# motor_ic.net
KiCad netlist of a schematic drawn in EAGLE
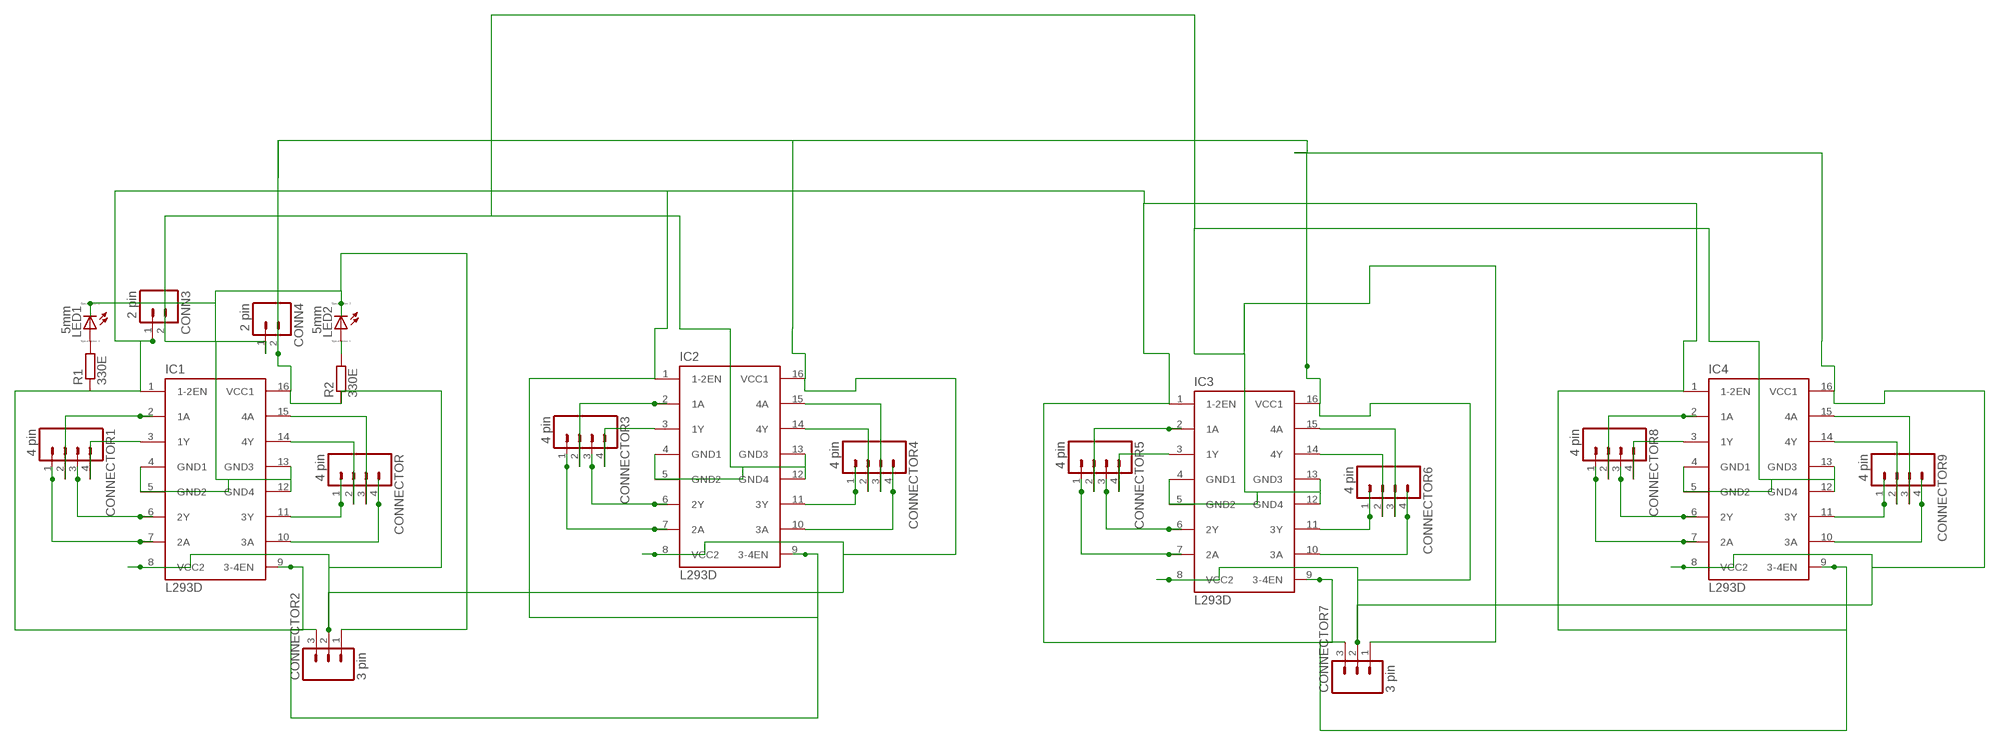
[diagram p0: schematic, sheet 1]

(export (version "E")
  (design (tool "Eeschema 10.0.6"))
  (components
    (comp (ref "CONN3")
      (value "2 pin")
      (footprint "eagle-import:02P")
      (libsource (lib "eagle-import") (part "M02"))
    )
    (comp (ref "CONN4")
      (value "2 pin")
      (footprint "eagle-import:02P")
      (libsource (lib "eagle-import") (part "M02"))
    )
    (comp (ref "CONNECTOR")
      (value "4 pin")
      (footprint "eagle-import:04P")
      (libsource (lib "eagle-import") (part "M04"))
    )
    (comp (ref "CONNECTOR1")
      (value "4 pin")
      (footprint "eagle-import:04P")
      (libsource (lib "eagle-import") (part "M04"))
    )
    (comp (ref "CONNECTOR2")
      (value "3 pin")
      (footprint "eagle-import:03P")
      (libsource (lib "eagle-import") (part "M03"))
    )
    (comp (ref "CONNECTOR3")
      (value "4 pin")
      (footprint "eagle-import:04P")
      (libsource (lib "eagle-import") (part "M04"))
    )
    (comp (ref "CONNECTOR4")
      (value "4 pin")
      (footprint "eagle-import:04P")
      (libsource (lib "eagle-import") (part "M04"))
    )
    (comp (ref "CONNECTOR5")
      (value "4 pin")
      (footprint "eagle-import:04P")
      (libsource (lib "eagle-import") (part "M04"))
    )
    (comp (ref "CONNECTOR6")
      (value "4 pin")
      (footprint "eagle-import:04P")
      (libsource (lib "eagle-import") (part "M04"))
    )
    (comp (ref "CONNECTOR7")
      (value "3 pin")
      (footprint "eagle-import:03P")
      (libsource (lib "eagle-import") (part "M03"))
    )
    (comp (ref "CONNECTOR8")
      (value "4 pin")
      (footprint "eagle-import:04P")
      (libsource (lib "eagle-import") (part "M04"))
    )
    (comp (ref "CONNECTOR9")
      (value "4 pin")
      (footprint "eagle-import:04P")
      (libsource (lib "eagle-import") (part "M04"))
    )
    (comp (ref "IC1")
      (value "L293D")
      (footprint "eagle-import:DIL16")
      (libsource (lib "eagle-import") (part "L293D"))
    )
    (comp (ref "IC2")
      (value "L293D")
      (footprint "eagle-import:DIL16")
      (libsource (lib "eagle-import") (part "L293D"))
    )
    (comp (ref "IC3")
      (value "L293D")
      (footprint "eagle-import:DIL16")
      (libsource (lib "eagle-import") (part "L293D"))
    )
    (comp (ref "IC4")
      (value "L293D")
      (footprint "eagle-import:DIL16")
      (libsource (lib "eagle-import") (part "L293D"))
    )
    (comp (ref "LED1")
      (value "5mm")
      (footprint "eagle-import:LED_LD260")
      (libsource (lib "eagle-import") (part "LED_ELD260"))
    )
    (comp (ref "LED2")
      (value "5mm")
      (footprint "eagle-import:LED_LD260")
      (libsource (lib "eagle-import") (part "LED_ELD260"))
    )
    (comp (ref "R1")
      (value "330E")
      (footprint "eagle-import:0204_7")
      (libsource (lib "eagle-import") (part "R-EU_0204/7"))
    )
    (comp (ref "R2")
      (value "330E")
      (footprint "eagle-import:0204_7")
      (libsource (lib "eagle-import") (part "R-EU_0204/7"))
    )
  )
  (nets
    (net (code "1") (name "Net-(IC1-1-2EN)") (class "Default")
      (node (ref "CONN3") (pin "1") (pinfunction "1_1") (pintype "passive"))
      (node (ref "CONNECTOR2") (pin "3") (pinfunction "3_3") (pintype "passive"))
      (node (ref "CONNECTOR7") (pin "3") (pinfunction "3_3") (pintype "passive"))
      (node (ref "IC1") (pin "1") (pinfunction "1-2EN_1") (pintype "input"))
      (node (ref "IC1") (pin "9") (pinfunction "3-4EN_9") (pintype "input"))
      (node (ref "IC2") (pin "1") (pinfunction "1-2EN_1") (pintype "input"))
      (node (ref "IC2") (pin "9") (pinfunction "3-4EN_9") (pintype "input"))
      (node (ref "IC3") (pin "1") (pinfunction "1-2EN_1") (pintype "input"))
      (node (ref "IC3") (pin "9") (pinfunction "3-4EN_9") (pintype "input"))
      (node (ref "IC4") (pin "1") (pinfunction "1-2EN_1") (pintype "input"))
      (node (ref "IC4") (pin "9") (pinfunction "3-4EN_9") (pintype "input"))
      (node (ref "R1") (pin "1") (pinfunction "1_1") (pintype "passive"))
    )
    (net (code "2") (name "Net-(IC1-1A)") (class "Default")
      (node (ref "CONNECTOR1") (pin "2") (pinfunction "2_2") (pintype "passive"))
      (node (ref "IC1") (pin "2") (pinfunction "1A_2") (pintype "input"))
    )
    (net (code "3") (name "Net-(IC1-1Y)") (class "Default")
      (node (ref "CONNECTOR1") (pin "4") (pinfunction "4_4") (pintype "passive"))
      (node (ref "IC1") (pin "3") (pinfunction "1Y_3") (pintype "output"))
    )
    (net (code "4") (name "Net-(IC1-2A)") (class "Default")
      (node (ref "CONNECTOR1") (pin "1") (pinfunction "1_1") (pintype "passive"))
      (node (ref "IC1") (pin "7") (pinfunction "2A_7") (pintype "input"))
    )
    (net (code "5") (name "Net-(IC1-2Y)") (class "Default")
      (node (ref "CONNECTOR1") (pin "3") (pinfunction "3_3") (pintype "passive"))
      (node (ref "IC1") (pin "6") (pinfunction "2Y_6") (pintype "output"))
    )
    (net (code "6") (name "Net-(IC1-3A)") (class "Default")
      (node (ref "CONNECTOR") (pin "4") (pinfunction "4_4") (pintype "passive"))
      (node (ref "IC1") (pin "10") (pinfunction "3A_10") (pintype "input"))
    )
    (net (code "7") (name "Net-(IC1-3Y)") (class "Default")
      (node (ref "CONNECTOR") (pin "1") (pinfunction "1_1") (pintype "passive"))
      (node (ref "IC1") (pin "11") (pinfunction "3Y_11") (pintype "output"))
    )
    (net (code "8") (name "Net-(IC1-4A)") (class "Default")
      (node (ref "CONNECTOR") (pin "3") (pinfunction "3_3") (pintype "passive"))
      (node (ref "IC1") (pin "15") (pinfunction "4A_15") (pintype "input"))
    )
    (net (code "9") (name "Net-(IC1-4Y)") (class "Default")
      (node (ref "CONNECTOR") (pin "2") (pinfunction "2_2") (pintype "passive"))
      (node (ref "IC1") (pin "14") (pinfunction "4Y_14") (pintype "output"))
    )
    (net (code "10") (name "Net-(IC1-GND1)") (class "Default")
      (node (ref "CONN3") (pin "2") (pinfunction "2_2") (pintype "passive"))
      (node (ref "CONN4") (pin "1") (pinfunction "1_1") (pintype "passive"))
      (node (ref "CONNECTOR2") (pin "1") (pinfunction "1_1") (pintype "passive"))
      (node (ref "CONNECTOR7") (pin "1") (pinfunction "1_1") (pintype "passive"))
      (node (ref "IC1") (pin "12") (pinfunction "GND4_12") (pintype "power_in"))
      (node (ref "IC1") (pin "13") (pinfunction "GND3_13") (pintype "power_in"))
      (node (ref "IC1") (pin "4") (pinfunction "GND1_4") (pintype "power_in"))
      (node (ref "IC1") (pin "5") (pinfunction "GND2_5") (pintype "power_in"))
      (node (ref "IC2") (pin "12") (pinfunction "GND4_12") (pintype "power_in"))
      (node (ref "IC2") (pin "13") (pinfunction "GND3_13") (pintype "power_in"))
      (node (ref "IC2") (pin "4") (pinfunction "GND1_4") (pintype "power_in"))
      (node (ref "IC2") (pin "5") (pinfunction "GND2_5") (pintype "power_in"))
      (node (ref "IC3") (pin "12") (pinfunction "GND4_12") (pintype "power_in"))
      (node (ref "IC3") (pin "13") (pinfunction "GND3_13") (pintype "power_in"))
      (node (ref "IC3") (pin "4") (pinfunction "GND1_4") (pintype "power_in"))
      (node (ref "IC3") (pin "5") (pinfunction "GND2_5") (pintype "power_in"))
      (node (ref "IC4") (pin "12") (pinfunction "GND4_12") (pintype "power_in"))
      (node (ref "IC4") (pin "13") (pinfunction "GND3_13") (pintype "power_in"))
      (node (ref "IC4") (pin "4") (pinfunction "GND1_4") (pintype "power_in"))
      (node (ref "IC4") (pin "5") (pinfunction "GND2_5") (pintype "power_in"))
      (node (ref "LED1") (pin "K") (pinfunction "C_K") (pintype "passive"))
      (node (ref "LED2") (pin "K") (pinfunction "C_K") (pintype "passive"))
    )
    (net (code "11") (name "Net-(IC1-VCC1)") (class "Default")
      (node (ref "CONN4") (pin "2") (pinfunction "2_2") (pintype "passive"))
      (node (ref "CONNECTOR2") (pin "2") (pinfunction "2_2") (pintype "passive"))
      (node (ref "CONNECTOR7") (pin "2") (pinfunction "2_2") (pintype "passive"))
      (node (ref "IC1") (pin "16") (pinfunction "VCC1_16") (pintype "power_in"))
      (node (ref "IC1") (pin "8") (pinfunction "VCC2_8") (pintype "power_in"))
      (node (ref "IC2") (pin "16") (pinfunction "VCC1_16") (pintype "power_in"))
      (node (ref "IC2") (pin "8") (pinfunction "VCC2_8") (pintype "power_in"))
      (node (ref "IC3") (pin "16") (pinfunction "VCC1_16") (pintype "power_in"))
      (node (ref "IC3") (pin "8") (pinfunction "VCC2_8") (pintype "power_in"))
      (node (ref "IC4") (pin "16") (pinfunction "VCC1_16") (pintype "power_in"))
      (node (ref "IC4") (pin "8") (pinfunction "VCC2_8") (pintype "power_in"))
      (node (ref "R2") (pin "1") (pinfunction "1_1") (pintype "passive"))
    )
    (net (code "12") (name "Net-(IC2-1A)") (class "Default")
      (node (ref "CONNECTOR3") (pin "2") (pinfunction "2_2") (pintype "passive"))
      (node (ref "IC2") (pin "2") (pinfunction "1A_2") (pintype "input"))
    )
    (net (code "13") (name "Net-(IC2-1Y)") (class "Default")
      (node (ref "CONNECTOR3") (pin "4") (pinfunction "4_4") (pintype "passive"))
      (node (ref "IC2") (pin "3") (pinfunction "1Y_3") (pintype "output"))
    )
    (net (code "14") (name "Net-(IC2-2A)") (class "Default")
      (node (ref "CONNECTOR3") (pin "1") (pinfunction "1_1") (pintype "passive"))
      (node (ref "IC2") (pin "7") (pinfunction "2A_7") (pintype "input"))
    )
    (net (code "15") (name "Net-(IC2-2Y)") (class "Default")
      (node (ref "CONNECTOR3") (pin "3") (pinfunction "3_3") (pintype "passive"))
      (node (ref "IC2") (pin "6") (pinfunction "2Y_6") (pintype "output"))
    )
    (net (code "16") (name "Net-(IC2-3A)") (class "Default")
      (node (ref "CONNECTOR4") (pin "4") (pinfunction "4_4") (pintype "passive"))
      (node (ref "IC2") (pin "10") (pinfunction "3A_10") (pintype "input"))
    )
    (net (code "17") (name "Net-(IC2-3Y)") (class "Default")
      (node (ref "CONNECTOR4") (pin "1") (pinfunction "1_1") (pintype "passive"))
      (node (ref "IC2") (pin "11") (pinfunction "3Y_11") (pintype "output"))
    )
    (net (code "18") (name "Net-(IC2-4A)") (class "Default")
      (node (ref "CONNECTOR4") (pin "3") (pinfunction "3_3") (pintype "passive"))
      (node (ref "IC2") (pin "15") (pinfunction "4A_15") (pintype "input"))
    )
    (net (code "19") (name "Net-(IC2-4Y)") (class "Default")
      (node (ref "CONNECTOR4") (pin "2") (pinfunction "2_2") (pintype "passive"))
      (node (ref "IC2") (pin "14") (pinfunction "4Y_14") (pintype "output"))
    )
    (net (code "20") (name "Net-(IC3-1A)") (class "Default")
      (node (ref "CONNECTOR5") (pin "2") (pinfunction "2_2") (pintype "passive"))
      (node (ref "IC3") (pin "2") (pinfunction "1A_2") (pintype "input"))
    )
    (net (code "21") (name "Net-(IC3-1Y)") (class "Default")
      (node (ref "CONNECTOR5") (pin "4") (pinfunction "4_4") (pintype "passive"))
      (node (ref "IC3") (pin "3") (pinfunction "1Y_3") (pintype "output"))
    )
    (net (code "22") (name "Net-(IC3-2A)") (class "Default")
      (node (ref "CONNECTOR5") (pin "1") (pinfunction "1_1") (pintype "passive"))
      (node (ref "IC3") (pin "7") (pinfunction "2A_7") (pintype "input"))
    )
    (net (code "23") (name "Net-(IC3-2Y)") (class "Default")
      (node (ref "CONNECTOR5") (pin "3") (pinfunction "3_3") (pintype "passive"))
      (node (ref "IC3") (pin "6") (pinfunction "2Y_6") (pintype "output"))
    )
    (net (code "24") (name "Net-(IC3-3A)") (class "Default")
      (node (ref "CONNECTOR6") (pin "4") (pinfunction "4_4") (pintype "passive"))
      (node (ref "IC3") (pin "10") (pinfunction "3A_10") (pintype "input"))
    )
    (net (code "25") (name "Net-(IC3-3Y)") (class "Default")
      (node (ref "CONNECTOR6") (pin "1") (pinfunction "1_1") (pintype "passive"))
      (node (ref "IC3") (pin "11") (pinfunction "3Y_11") (pintype "output"))
    )
    (net (code "26") (name "Net-(IC3-4A)") (class "Default")
      (node (ref "CONNECTOR6") (pin "3") (pinfunction "3_3") (pintype "passive"))
      (node (ref "IC3") (pin "15") (pinfunction "4A_15") (pintype "input"))
    )
    (net (code "27") (name "Net-(IC3-4Y)") (class "Default")
      (node (ref "CONNECTOR6") (pin "2") (pinfunction "2_2") (pintype "passive"))
      (node (ref "IC3") (pin "14") (pinfunction "4Y_14") (pintype "output"))
    )
    (net (code "28") (name "Net-(IC4-1A)") (class "Default")
      (node (ref "CONNECTOR8") (pin "2") (pinfunction "2_2") (pintype "passive"))
      (node (ref "IC4") (pin "2") (pinfunction "1A_2") (pintype "input"))
    )
    (net (code "29") (name "Net-(IC4-1Y)") (class "Default")
      (node (ref "CONNECTOR8") (pin "4") (pinfunction "4_4") (pintype "passive"))
      (node (ref "IC4") (pin "3") (pinfunction "1Y_3") (pintype "output"))
    )
    (net (code "30") (name "Net-(IC4-2A)") (class "Default")
      (node (ref "CONNECTOR8") (pin "1") (pinfunction "1_1") (pintype "passive"))
      (node (ref "IC4") (pin "7") (pinfunction "2A_7") (pintype "input"))
    )
    (net (code "31") (name "Net-(IC4-2Y)") (class "Default")
      (node (ref "CONNECTOR8") (pin "3") (pinfunction "3_3") (pintype "passive"))
      (node (ref "IC4") (pin "6") (pinfunction "2Y_6") (pintype "output"))
    )
    (net (code "32") (name "Net-(IC4-3A)") (class "Default")
      (node (ref "CONNECTOR9") (pin "4") (pinfunction "4_4") (pintype "passive"))
      (node (ref "IC4") (pin "10") (pinfunction "3A_10") (pintype "input"))
    )
    (net (code "33") (name "Net-(IC4-3Y)") (class "Default")
      (node (ref "CONNECTOR9") (pin "1") (pinfunction "1_1") (pintype "passive"))
      (node (ref "IC4") (pin "11") (pinfunction "3Y_11") (pintype "output"))
    )
    (net (code "34") (name "Net-(IC4-4A)") (class "Default")
      (node (ref "CONNECTOR9") (pin "3") (pinfunction "3_3") (pintype "passive"))
      (node (ref "IC4") (pin "15") (pinfunction "4A_15") (pintype "input"))
    )
    (net (code "35") (name "Net-(IC4-4Y)") (class "Default")
      (node (ref "CONNECTOR9") (pin "2") (pinfunction "2_2") (pintype "passive"))
      (node (ref "IC4") (pin "14") (pinfunction "4Y_14") (pintype "output"))
    )
    (net (code "36") (name "Net-(LED1-PadA)") (class "Default")
      (node (ref "LED1") (pin "A") (pinfunction "A_A") (pintype "passive"))
      (node (ref "R1") (pin "2") (pinfunction "2_2") (pintype "passive"))
    )
    (net (code "37") (name "Net-(LED2-PadA)") (class "Default")
      (node (ref "LED2") (pin "A") (pinfunction "A_A") (pintype "passive"))
      (node (ref "R2") (pin "2") (pinfunction "2_2") (pintype "passive"))
    )
  )
)
